# x8-oDisplayV1_3.net
KiCad netlist of a schematic drawn in EAGLE
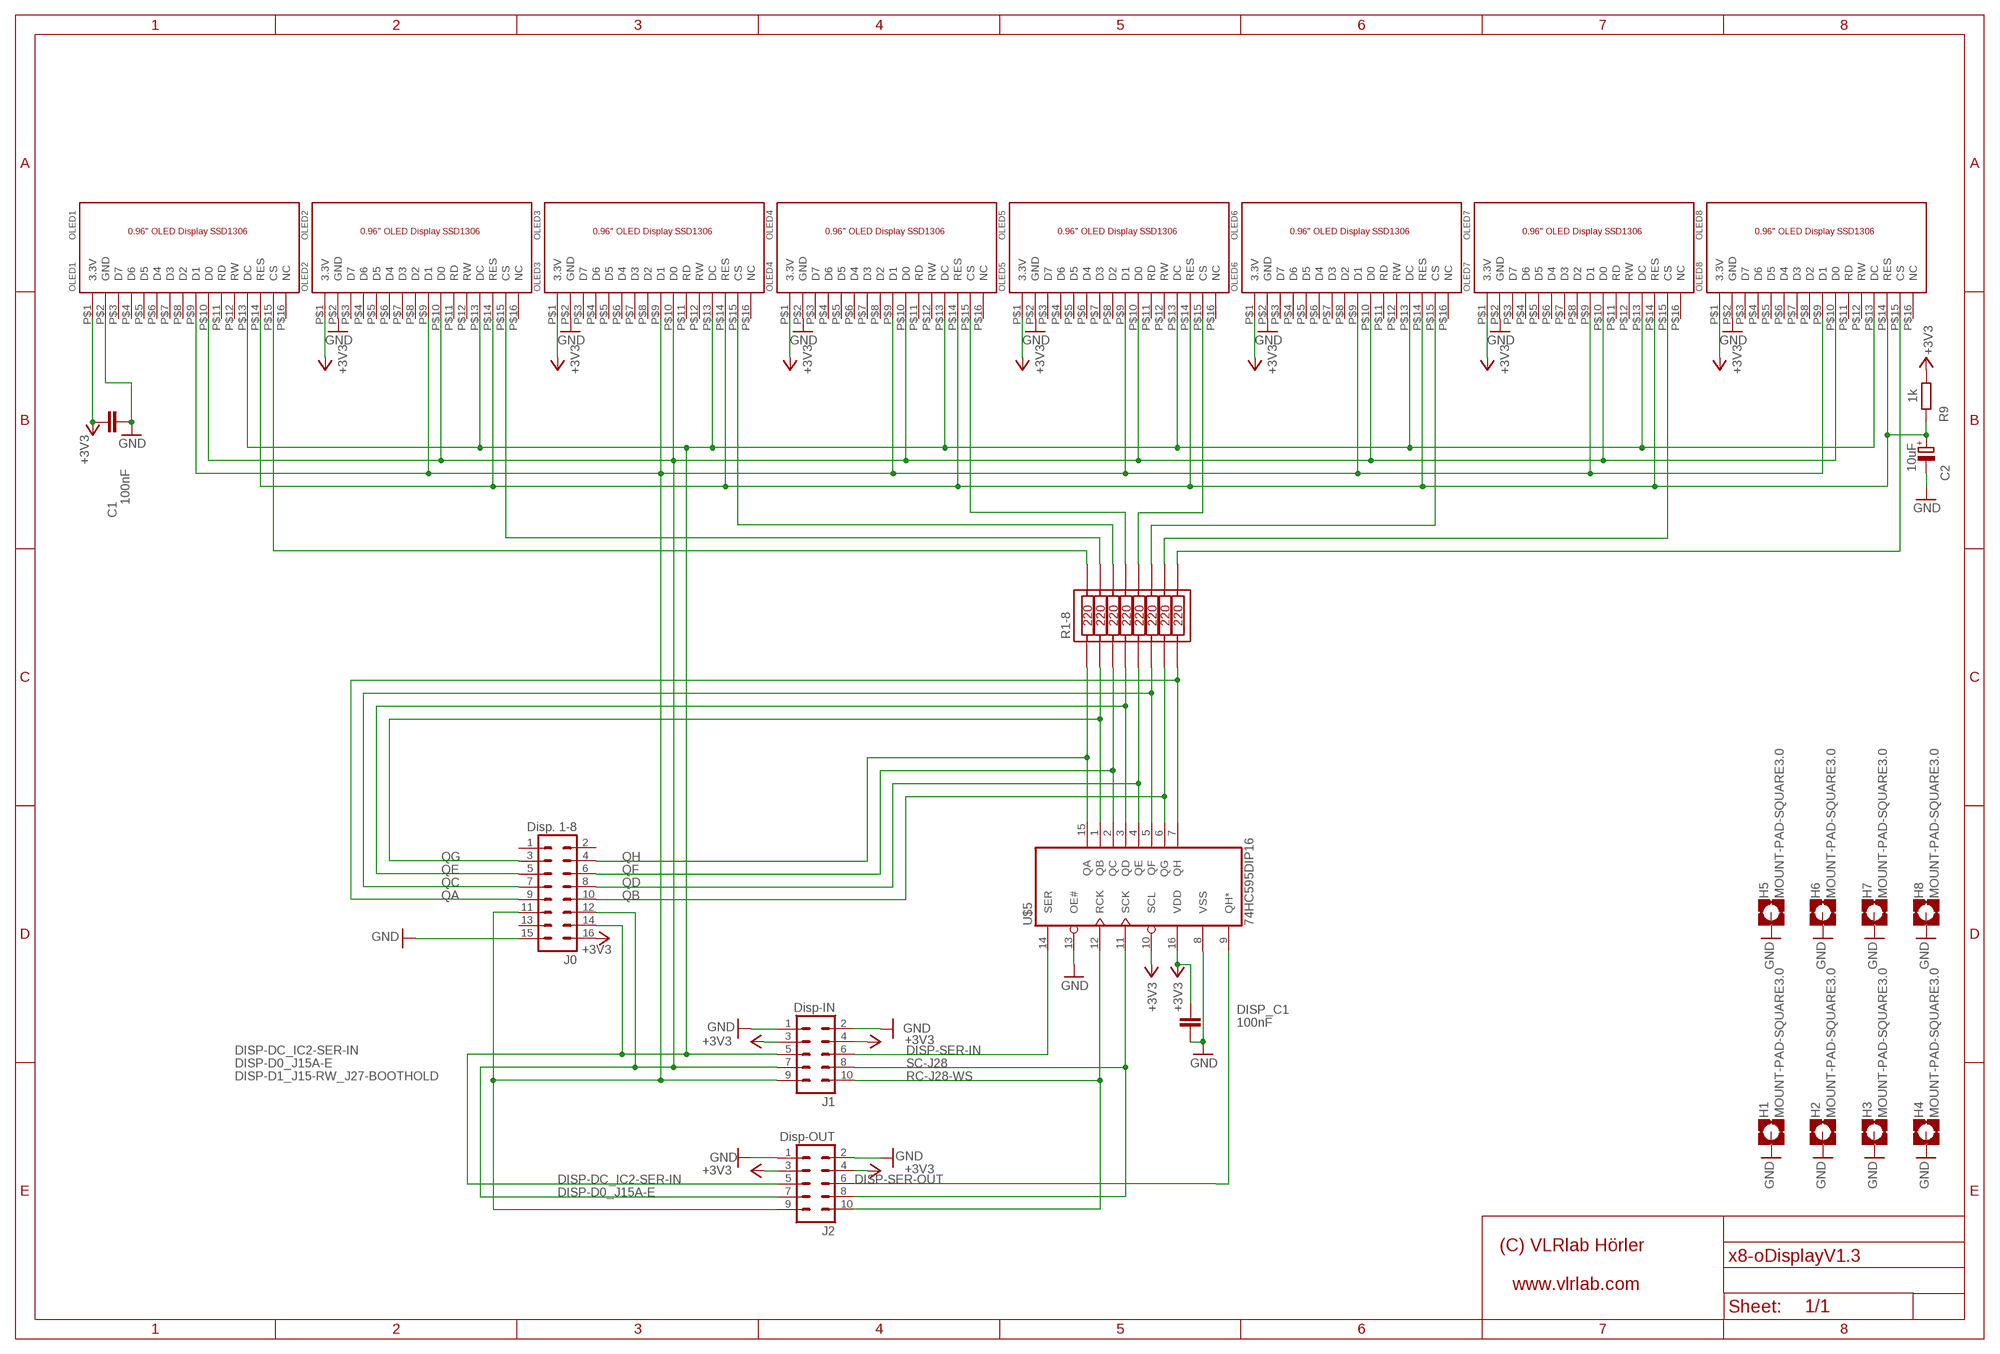
[diagram p0: schematic, sheet 1]

(export (version "E")
  (design (tool "Eeschema 10.0.6"))
  (components
    (comp (ref "C1")
      (value "100nF")
      (footprint "eagle-import:C5B3")
      (libsource (lib "eagle-import") (part "C5/3"))
    )
    (comp (ref "C2")
      (value "10uF")
      (footprint "eagle-import:E2,5-6")
      (libsource (lib "eagle-import") (part "CPOL-EUE2.5-6"))
    )
    (comp (ref "DISP_C1")
      (value "100nF")
      (footprint "eagle-import:C5B3")
      (libsource (lib "eagle-import") (part "C5/3"))
    )
    (comp (ref "H1")
      (value "MOUNT-PAD-SQUARE3.0")
      (footprint "eagle-import:3,0-PAD-SQUARE")
      (libsource (lib "eagle-import") (part "MOUNT-PAD-SQUARE3.0"))
    )
    (comp (ref "H2")
      (value "MOUNT-PAD-SQUARE3.0")
      (footprint "eagle-import:3,0-PAD-SQUARE")
      (libsource (lib "eagle-import") (part "MOUNT-PAD-SQUARE3.0"))
    )
    (comp (ref "H3")
      (value "MOUNT-PAD-SQUARE3.0")
      (footprint "eagle-import:3,0-PAD-SQUARE")
      (libsource (lib "eagle-import") (part "MOUNT-PAD-SQUARE3.0"))
    )
    (comp (ref "H4")
      (value "MOUNT-PAD-SQUARE3.0")
      (footprint "eagle-import:3,0-PAD-SQUARE")
      (libsource (lib "eagle-import") (part "MOUNT-PAD-SQUARE3.0"))
    )
    (comp (ref "H5")
      (value "MOUNT-PAD-SQUARE3.0")
      (footprint "eagle-import:3,0-PAD-SQUARE")
      (libsource (lib "eagle-import") (part "MOUNT-PAD-SQUARE3.0"))
    )
    (comp (ref "H6")
      (value "MOUNT-PAD-SQUARE3.0")
      (footprint "eagle-import:3,0-PAD-SQUARE")
      (libsource (lib "eagle-import") (part "MOUNT-PAD-SQUARE3.0"))
    )
    (comp (ref "H7")
      (value "MOUNT-PAD-SQUARE3.0")
      (footprint "eagle-import:3,0-PAD-SQUARE")
      (libsource (lib "eagle-import") (part "MOUNT-PAD-SQUARE3.0"))
    )
    (comp (ref "H8")
      (value "MOUNT-PAD-SQUARE3.0")
      (footprint "eagle-import:3,0-PAD-SQUARE")
      (libsource (lib "eagle-import") (part "MOUNT-PAD-SQUARE3.0"))
    )
    (comp (ref "J0")
      (value "Disp. 1-8")
      (footprint "eagle-import:ML16")
      (libsource (lib "eagle-import") (part "ML16"))
    )
    (comp (ref "J1")
      (value "Disp-IN")
      (footprint "eagle-import:ML10")
      (libsource (lib "eagle-import") (part "ML10"))
    )
    (comp (ref "J2")
      (value "Disp-OUT")
      (footprint "eagle-import:ML10")
      (libsource (lib "eagle-import") (part "ML10"))
    )
    (comp (ref "OLED1")
      (value "OLED1")
      (footprint "eagle-import:0.96_")
      (libsource (lib "eagle-import") (part "0.96{dblquote}OLED"))
    )
    (comp (ref "OLED2")
      (value "OLED2")
      (footprint "eagle-import:0.96_")
      (libsource (lib "eagle-import") (part "0.96{dblquote}OLED"))
    )
    (comp (ref "OLED3")
      (value "OLED3")
      (footprint "eagle-import:0.96_")
      (libsource (lib "eagle-import") (part "0.96{dblquote}OLED"))
    )
    (comp (ref "OLED4")
      (value "OLED4")
      (footprint "eagle-import:0.96_")
      (libsource (lib "eagle-import") (part "0.96{dblquote}OLED"))
    )
    (comp (ref "OLED5")
      (value "OLED5")
      (footprint "eagle-import:0.96_")
      (libsource (lib "eagle-import") (part "0.96{dblquote}OLED"))
    )
    (comp (ref "OLED6")
      (value "OLED6")
      (footprint "eagle-import:0.96_")
      (libsource (lib "eagle-import") (part "0.96{dblquote}OLED"))
    )
    (comp (ref "OLED7")
      (value "OLED7")
      (footprint "eagle-import:0.96_")
      (libsource (lib "eagle-import") (part "0.96{dblquote}OLED"))
    )
    (comp (ref "OLED8")
      (value "OLED8")
      (footprint "eagle-import:0.96_")
      (libsource (lib "eagle-import") (part "0.96{dblquote}OLED"))
    )
    (comp (ref "R1-8")
      (value "4116R")
      (footprint "eagle-import:DIL16")
      (libsource (lib "eagle-import") (part "4116R"))
    )
    (comp (ref "R9")
      (value "1k")
      (footprint "eagle-import:0204_7")
      (libsource (lib "eagle-import") (part "R-EU_0204/7"))
    )
    (comp (ref "U$5")
      (value "74HC595DIP16")
      (footprint "eagle-import:DIL16")
      (libsource (lib "eagle-import") (part "74HC595DIP16"))
    )
  )
  (nets
    (net (code "1") (name "+3V3") (class "Default")
      (node (ref "C1") (pin "1") (pinfunction "1_1") (pintype "passive"))
      (node (ref "DISP_C1") (pin "1") (pinfunction "1_1") (pintype "passive"))
      (node (ref "J0") (pin "16") (pinfunction "16_16") (pintype "passive"))
      (node (ref "J1") (pin "3") (pinfunction "3_3") (pintype "passive"))
      (node (ref "J1") (pin "4") (pinfunction "4_4") (pintype "passive"))
      (node (ref "J2") (pin "3") (pinfunction "3_3") (pintype "passive"))
      (node (ref "J2") (pin "4") (pinfunction "4_4") (pintype "passive"))
      (node (ref "OLED1") (pin "P$1") (pinfunction "3.3V_P$1") (pintype "bidirectional"))
      (node (ref "OLED2") (pin "P$1") (pinfunction "3.3V_P$1") (pintype "bidirectional"))
      (node (ref "OLED3") (pin "P$1") (pinfunction "3.3V_P$1") (pintype "bidirectional"))
      (node (ref "OLED4") (pin "P$1") (pinfunction "3.3V_P$1") (pintype "bidirectional"))
      (node (ref "OLED5") (pin "P$1") (pinfunction "3.3V_P$1") (pintype "bidirectional"))
      (node (ref "OLED6") (pin "P$1") (pinfunction "3.3V_P$1") (pintype "bidirectional"))
      (node (ref "OLED7") (pin "P$1") (pinfunction "3.3V_P$1") (pintype "bidirectional"))
      (node (ref "OLED8") (pin "P$1") (pinfunction "3.3V_P$1") (pintype "bidirectional"))
      (node (ref "R9") (pin "2") (pinfunction "2_2") (pintype "passive"))
      (node (ref "U$5") (pin "10") (pinfunction "SCL_10") (pintype "input"))
      (node (ref "U$5") (pin "16") (pinfunction "VDD_16") (pintype "power_in"))
    )
    (net (code "2") (name "/DISP-D0_J15A-E") (class "Default")
      (node (ref "J0") (pin "12") (pinfunction "12_12") (pintype "passive"))
      (node (ref "J1") (pin "7") (pinfunction "7_7") (pintype "passive"))
      (node (ref "J2") (pin "7") (pinfunction "7_7") (pintype "passive"))
      (node (ref "OLED1") (pin "P$10") (pinfunction "D0_P$10") (pintype "bidirectional"))
      (node (ref "OLED2") (pin "P$10") (pinfunction "D0_P$10") (pintype "bidirectional"))
      (node (ref "OLED3") (pin "P$10") (pinfunction "D0_P$10") (pintype "bidirectional"))
      (node (ref "OLED4") (pin "P$10") (pinfunction "D0_P$10") (pintype "bidirectional"))
      (node (ref "OLED5") (pin "P$10") (pinfunction "D0_P$10") (pintype "bidirectional"))
      (node (ref "OLED6") (pin "P$10") (pinfunction "D0_P$10") (pintype "bidirectional"))
      (node (ref "OLED7") (pin "P$10") (pinfunction "D0_P$10") (pintype "bidirectional"))
      (node (ref "OLED8") (pin "P$10") (pinfunction "D0_P$10") (pintype "bidirectional"))
    )
    (net (code "3") (name "/DISP-D1_J15-RW_J27-BOOTHOLD") (class "Default")
      (node (ref "J0") (pin "11") (pinfunction "11_11") (pintype "passive"))
      (node (ref "J1") (pin "9") (pinfunction "9_9") (pintype "passive"))
      (node (ref "J2") (pin "9") (pinfunction "9_9") (pintype "passive"))
      (node (ref "OLED1") (pin "P$9") (pinfunction "D1_P$9") (pintype "bidirectional"))
      (node (ref "OLED2") (pin "P$9") (pinfunction "D1_P$9") (pintype "bidirectional"))
      (node (ref "OLED3") (pin "P$9") (pinfunction "D1_P$9") (pintype "bidirectional"))
      (node (ref "OLED4") (pin "P$9") (pinfunction "D1_P$9") (pintype "bidirectional"))
      (node (ref "OLED5") (pin "P$9") (pinfunction "D1_P$9") (pintype "bidirectional"))
      (node (ref "OLED6") (pin "P$9") (pinfunction "D1_P$9") (pintype "bidirectional"))
      (node (ref "OLED7") (pin "P$9") (pinfunction "D1_P$9") (pintype "bidirectional"))
      (node (ref "OLED8") (pin "P$9") (pinfunction "D1_P$9") (pintype "bidirectional"))
    )
    (net (code "4") (name "/DISP-DC_IC2-SER-IN") (class "Default")
      (node (ref "J0") (pin "14") (pinfunction "14_14") (pintype "passive"))
      (node (ref "J1") (pin "5") (pinfunction "5_5") (pintype "passive"))
      (node (ref "J2") (pin "5") (pinfunction "5_5") (pintype "passive"))
      (node (ref "OLED1") (pin "P$13") (pinfunction "DC_P$13") (pintype "bidirectional"))
      (node (ref "OLED2") (pin "P$13") (pinfunction "DC_P$13") (pintype "bidirectional"))
      (node (ref "OLED3") (pin "P$13") (pinfunction "DC_P$13") (pintype "bidirectional"))
      (node (ref "OLED4") (pin "P$13") (pinfunction "DC_P$13") (pintype "bidirectional"))
      (node (ref "OLED5") (pin "P$13") (pinfunction "DC_P$13") (pintype "bidirectional"))
      (node (ref "OLED6") (pin "P$13") (pinfunction "DC_P$13") (pintype "bidirectional"))
      (node (ref "OLED7") (pin "P$13") (pinfunction "DC_P$13") (pintype "bidirectional"))
      (node (ref "OLED8") (pin "P$13") (pinfunction "DC_P$13") (pintype "bidirectional"))
    )
    (net (code "5") (name "/DISP-SER-IN") (class "Default")
      (node (ref "J1") (pin "6") (pinfunction "6_6") (pintype "passive"))
      (node (ref "U$5") (pin "14") (pinfunction "SER_14") (pintype "input"))
    )
    (net (code "6") (name "/DISP-SER-OUT") (class "Default")
      (node (ref "J2") (pin "6") (pinfunction "6_6") (pintype "passive"))
      (node (ref "U$5") (pin "9") (pinfunction "QH*_9") (pintype "tri_state"))
    )
    (net (code "7") (name "/QA") (class "Default")
      (node (ref "J0") (pin "9") (pinfunction "9_9") (pintype "passive"))
      (node (ref "R1-8") (pin "16") (pinfunction "P$16_16") (pintype "bidirectional"))
      (node (ref "U$5") (pin "7") (pinfunction "QH_7") (pintype "tri_state"))
    )
    (net (code "8") (name "/QB") (class "Default")
      (node (ref "J0") (pin "10") (pinfunction "10_10") (pintype "passive"))
      (node (ref "R1-8") (pin "15") (pinfunction "P$15_15") (pintype "bidirectional"))
      (node (ref "U$5") (pin "6") (pinfunction "QG_6") (pintype "tri_state"))
    )
    (net (code "9") (name "/QC") (class "Default")
      (node (ref "J0") (pin "7") (pinfunction "7_7") (pintype "passive"))
      (node (ref "R1-8") (pin "14") (pinfunction "P$14_14") (pintype "bidirectional"))
      (node (ref "U$5") (pin "5") (pinfunction "QF_5") (pintype "tri_state"))
    )
    (net (code "10") (name "/QD") (class "Default")
      (node (ref "J0") (pin "8") (pinfunction "8_8") (pintype "passive"))
      (node (ref "R1-8") (pin "13") (pinfunction "P$13_13") (pintype "bidirectional"))
      (node (ref "U$5") (pin "4") (pinfunction "QE_4") (pintype "tri_state"))
    )
    (net (code "11") (name "/QE") (class "Default")
      (node (ref "J0") (pin "5") (pinfunction "5_5") (pintype "passive"))
      (node (ref "R1-8") (pin "12") (pinfunction "P$12_12") (pintype "bidirectional"))
      (node (ref "U$5") (pin "3") (pinfunction "QD_3") (pintype "tri_state"))
    )
    (net (code "12") (name "/QF") (class "Default")
      (node (ref "J0") (pin "6") (pinfunction "6_6") (pintype "passive"))
      (node (ref "R1-8") (pin "11") (pinfunction "P$11_11") (pintype "bidirectional"))
      (node (ref "U$5") (pin "2") (pinfunction "QC_2") (pintype "tri_state"))
    )
    (net (code "13") (name "/QG") (class "Default")
      (node (ref "J0") (pin "3") (pinfunction "3_3") (pintype "passive"))
      (node (ref "R1-8") (pin "10") (pinfunction "P$10_10") (pintype "bidirectional"))
      (node (ref "U$5") (pin "1") (pinfunction "QB_1") (pintype "tri_state"))
    )
    (net (code "14") (name "/QH") (class "Default")
      (node (ref "J0") (pin "4") (pinfunction "4_4") (pintype "passive"))
      (node (ref "R1-8") (pin "9") (pinfunction "P$9_9") (pintype "bidirectional"))
      (node (ref "U$5") (pin "15") (pinfunction "QA_15") (pintype "tri_state"))
    )
    (net (code "15") (name "/RC-J28-WS") (class "Default")
      (node (ref "J1") (pin "10") (pinfunction "10_10") (pintype "passive"))
      (node (ref "J2") (pin "10") (pinfunction "10_10") (pintype "passive"))
      (node (ref "U$5") (pin "12") (pinfunction "RCK_12") (pintype "input"))
    )
    (net (code "16") (name "/SC-J28") (class "Default")
      (node (ref "J1") (pin "8") (pinfunction "8_8") (pintype "passive"))
      (node (ref "J2") (pin "8") (pinfunction "8_8") (pintype "passive"))
      (node (ref "U$5") (pin "11") (pinfunction "SCK_11") (pintype "input"))
    )
    (net (code "17") (name "GND") (class "Default")
      (node (ref "C1") (pin "2") (pinfunction "2_2") (pintype "passive"))
      (node (ref "C2") (pin "-") (pinfunction "-_-") (pintype "passive"))
      (node (ref "DISP_C1") (pin "2") (pinfunction "2_2") (pintype "passive"))
      (node (ref "H1") (pin "B3,0") (pinfunction "MOUNT_B3,0") (pintype "passive"))
      (node (ref "H2") (pin "B3,0") (pinfunction "MOUNT_B3,0") (pintype "passive"))
      (node (ref "H3") (pin "B3,0") (pinfunction "MOUNT_B3,0") (pintype "passive"))
      (node (ref "H4") (pin "B3,0") (pinfunction "MOUNT_B3,0") (pintype "passive"))
      (node (ref "H5") (pin "B3,0") (pinfunction "MOUNT_B3,0") (pintype "passive"))
      (node (ref "H6") (pin "B3,0") (pinfunction "MOUNT_B3,0") (pintype "passive"))
      (node (ref "H7") (pin "B3,0") (pinfunction "MOUNT_B3,0") (pintype "passive"))
      (node (ref "H8") (pin "B3,0") (pinfunction "MOUNT_B3,0") (pintype "passive"))
      (node (ref "J0") (pin "15") (pinfunction "15_15") (pintype "passive"))
      (node (ref "J1") (pin "1") (pinfunction "1_1") (pintype "passive"))
      (node (ref "J1") (pin "2") (pinfunction "2_2") (pintype "passive"))
      (node (ref "J2") (pin "1") (pinfunction "1_1") (pintype "passive"))
      (node (ref "J2") (pin "2") (pinfunction "2_2") (pintype "passive"))
      (node (ref "OLED1") (pin "P$2") (pinfunction "GND_P$2") (pintype "bidirectional"))
      (node (ref "OLED2") (pin "P$2") (pinfunction "GND_P$2") (pintype "bidirectional"))
      (node (ref "OLED3") (pin "P$2") (pinfunction "GND_P$2") (pintype "bidirectional"))
      (node (ref "OLED4") (pin "P$2") (pinfunction "GND_P$2") (pintype "bidirectional"))
      (node (ref "OLED5") (pin "P$2") (pinfunction "GND_P$2") (pintype "bidirectional"))
      (node (ref "OLED6") (pin "P$2") (pinfunction "GND_P$2") (pintype "bidirectional"))
      (node (ref "OLED7") (pin "P$2") (pinfunction "GND_P$2") (pintype "bidirectional"))
      (node (ref "OLED8") (pin "P$2") (pinfunction "GND_P$2") (pintype "bidirectional"))
      (node (ref "U$5") (pin "13") (pinfunction "OE#_13") (pintype "input"))
      (node (ref "U$5") (pin "8") (pinfunction "VSS_8") (pintype "power_in"))
    )
    (net (code "18") (name "Net-(OLED1-CS)") (class "Default")
      (node (ref "OLED1") (pin "P$15") (pinfunction "CS_P$15") (pintype "bidirectional"))
      (node (ref "R1-8") (pin "1") (pinfunction "P$1_1") (pintype "bidirectional"))
    )
    (net (code "19") (name "Net-(OLED1-RES)") (class "Default")
      (node (ref "C2") (pin "+") (pinfunction "+_+") (pintype "passive"))
      (node (ref "OLED1") (pin "P$14") (pinfunction "RES_P$14") (pintype "bidirectional"))
      (node (ref "OLED2") (pin "P$14") (pinfunction "RES_P$14") (pintype "bidirectional"))
      (node (ref "OLED3") (pin "P$14") (pinfunction "RES_P$14") (pintype "bidirectional"))
      (node (ref "OLED4") (pin "P$14") (pinfunction "RES_P$14") (pintype "bidirectional"))
      (node (ref "OLED5") (pin "P$14") (pinfunction "RES_P$14") (pintype "bidirectional"))
      (node (ref "OLED6") (pin "P$14") (pinfunction "RES_P$14") (pintype "bidirectional"))
      (node (ref "OLED7") (pin "P$14") (pinfunction "RES_P$14") (pintype "bidirectional"))
      (node (ref "OLED8") (pin "P$14") (pinfunction "RES_P$14") (pintype "bidirectional"))
      (node (ref "R9") (pin "1") (pinfunction "1_1") (pintype "passive"))
    )
    (net (code "20") (name "Net-(OLED2-CS)") (class "Default")
      (node (ref "OLED2") (pin "P$15") (pinfunction "CS_P$15") (pintype "bidirectional"))
      (node (ref "R1-8") (pin "2") (pinfunction "P$2_2") (pintype "bidirectional"))
    )
    (net (code "21") (name "Net-(OLED3-CS)") (class "Default")
      (node (ref "OLED3") (pin "P$15") (pinfunction "CS_P$15") (pintype "bidirectional"))
      (node (ref "R1-8") (pin "3") (pinfunction "P$3_3") (pintype "bidirectional"))
    )
    (net (code "22") (name "Net-(OLED4-CS)") (class "Default")
      (node (ref "OLED4") (pin "P$15") (pinfunction "CS_P$15") (pintype "bidirectional"))
      (node (ref "R1-8") (pin "4") (pinfunction "P$4_4") (pintype "bidirectional"))
    )
    (net (code "23") (name "Net-(OLED5-CS)") (class "Default")
      (node (ref "OLED5") (pin "P$15") (pinfunction "CS_P$15") (pintype "bidirectional"))
      (node (ref "R1-8") (pin "5") (pinfunction "P$5_5") (pintype "bidirectional"))
    )
    (net (code "24") (name "Net-(OLED6-CS)") (class "Default")
      (node (ref "OLED6") (pin "P$15") (pinfunction "CS_P$15") (pintype "bidirectional"))
      (node (ref "R1-8") (pin "6") (pinfunction "P$6_6") (pintype "bidirectional"))
    )
    (net (code "25") (name "Net-(OLED7-CS)") (class "Default")
      (node (ref "OLED7") (pin "P$15") (pinfunction "CS_P$15") (pintype "bidirectional"))
      (node (ref "R1-8") (pin "7") (pinfunction "P$7_7") (pintype "bidirectional"))
    )
    (net (code "26") (name "Net-(OLED8-CS)") (class "Default")
      (node (ref "OLED8") (pin "P$15") (pinfunction "CS_P$15") (pintype "bidirectional"))
      (node (ref "R1-8") (pin "8") (pinfunction "P$8_8") (pintype "bidirectional"))
    )
    (net (code "27") (name "unconnected-(J0-Pad1)") (class "Default")
      (node (ref "J0") (pin "1") (pinfunction "1_1") (pintype "passive"))
    )
    (net (code "28") (name "unconnected-(J0-Pad2)") (class "Default")
      (node (ref "J0") (pin "2") (pinfunction "2_2") (pintype "passive"))
    )
    (net (code "29") (name "unconnected-(J0-Pad13)") (class "Default")
      (node (ref "J0") (pin "13") (pinfunction "13_13") (pintype "passive"))
    )
    (net (code "30") (name "unconnected-(OLED1-D2-PadP$8)") (class "Default")
      (node (ref "OLED1") (pin "P$8") (pinfunction "D2_P$8") (pintype "bidirectional"))
    )
    (net (code "31") (name "unconnected-(OLED1-D3-PadP$7)") (class "Default")
      (node (ref "OLED1") (pin "P$7") (pinfunction "D3_P$7") (pintype "bidirectional"))
    )
    (net (code "32") (name "unconnected-(OLED1-D4-PadP$6)") (class "Default")
      (node (ref "OLED1") (pin "P$6") (pinfunction "D4_P$6") (pintype "bidirectional"))
    )
    (net (code "33") (name "unconnected-(OLED1-D5-PadP$5)") (class "Default")
      (node (ref "OLED1") (pin "P$5") (pinfunction "D5_P$5") (pintype "bidirectional"))
    )
    (net (code "34") (name "unconnected-(OLED1-D6-PadP$4)") (class "Default")
      (node (ref "OLED1") (pin "P$4") (pinfunction "D6_P$4") (pintype "bidirectional"))
    )
    (net (code "35") (name "unconnected-(OLED1-D7-PadP$3)") (class "Default")
      (node (ref "OLED1") (pin "P$3") (pinfunction "D7_P$3") (pintype "bidirectional"))
    )
    (net (code "36") (name "unconnected-(OLED1-NC-PadP$16)") (class "Default")
      (node (ref "OLED1") (pin "P$16") (pinfunction "NC_P$16") (pintype "bidirectional"))
    )
    (net (code "37") (name "unconnected-(OLED1-RD-PadP$11)") (class "Default")
      (node (ref "OLED1") (pin "P$11") (pinfunction "RD_P$11") (pintype "bidirectional"))
    )
    (net (code "38") (name "unconnected-(OLED1-RW-PadP$12)") (class "Default")
      (node (ref "OLED1") (pin "P$12") (pinfunction "RW_P$12") (pintype "bidirectional"))
    )
    (net (code "39") (name "unconnected-(OLED2-D2-PadP$8)") (class "Default")
      (node (ref "OLED2") (pin "P$8") (pinfunction "D2_P$8") (pintype "bidirectional"))
    )
    (net (code "40") (name "unconnected-(OLED2-D3-PadP$7)") (class "Default")
      (node (ref "OLED2") (pin "P$7") (pinfunction "D3_P$7") (pintype "bidirectional"))
    )
    (net (code "41") (name "unconnected-(OLED2-D4-PadP$6)") (class "Default")
      (node (ref "OLED2") (pin "P$6") (pinfunction "D4_P$6") (pintype "bidirectional"))
    )
    (net (code "42") (name "unconnected-(OLED2-D5-PadP$5)") (class "Default")
      (node (ref "OLED2") (pin "P$5") (pinfunction "D5_P$5") (pintype "bidirectional"))
    )
    (net (code "43") (name "unconnected-(OLED2-D6-PadP$4)") (class "Default")
      (node (ref "OLED2") (pin "P$4") (pinfunction "D6_P$4") (pintype "bidirectional"))
    )
    (net (code "44") (name "unconnected-(OLED2-D7-PadP$3)") (class "Default")
      (node (ref "OLED2") (pin "P$3") (pinfunction "D7_P$3") (pintype "bidirectional"))
    )
    (net (code "45") (name "unconnected-(OLED2-NC-PadP$16)") (class "Default")
      (node (ref "OLED2") (pin "P$16") (pinfunction "NC_P$16") (pintype "bidirectional"))
    )
    (net (code "46") (name "unconnected-(OLED2-RD-PadP$11)") (class "Default")
      (node (ref "OLED2") (pin "P$11") (pinfunction "RD_P$11") (pintype "bidirectional"))
    )
    (net (code "47") (name "unconnected-(OLED2-RW-PadP$12)") (class "Default")
      (node (ref "OLED2") (pin "P$12") (pinfunction "RW_P$12") (pintype "bidirectional"))
    )
    (net (code "48") (name "unconnected-(OLED3-D2-PadP$8)") (class "Default")
      (node (ref "OLED3") (pin "P$8") (pinfunction "D2_P$8") (pintype "bidirectional"))
    )
    (net (code "49") (name "unconnected-(OLED3-D3-PadP$7)") (class "Default")
      (node (ref "OLED3") (pin "P$7") (pinfunction "D3_P$7") (pintype "bidirectional"))
    )
    (net (code "50") (name "unconnected-(OLED3-D4-PadP$6)") (class "Default")
      (node (ref "OLED3") (pin "P$6") (pinfunction "D4_P$6") (pintype "bidirectional"))
    )
    (net (code "51") (name "unconnected-(OLED3-D5-PadP$5)") (class "Default")
      (node (ref "OLED3") (pin "P$5") (pinfunction "D5_P$5") (pintype "bidirectional"))
    )
    (net (code "52") (name "unconnected-(OLED3-D6-PadP$4)") (class "Default")
      (node (ref "OLED3") (pin "P$4") (pinfunction "D6_P$4") (pintype "bidirectional"))
    )
    (net (code "53") (name "unconnected-(OLED3-D7-PadP$3)") (class "Default")
      (node (ref "OLED3") (pin "P$3") (pinfunction "D7_P$3") (pintype "bidirectional"))
    )
    (net (code "54") (name "unconnected-(OLED3-NC-PadP$16)") (class "Default")
      (node (ref "OLED3") (pin "P$16") (pinfunction "NC_P$16") (pintype "bidirectional"))
    )
    (net (code "55") (name "unconnected-(OLED3-RD-PadP$11)") (class "Default")
      (node (ref "OLED3") (pin "P$11") (pinfunction "RD_P$11") (pintype "bidirectional"))
    )
    (net (code "56") (name "unconnected-(OLED3-RW-PadP$12)") (class "Default")
      (node (ref "OLED3") (pin "P$12") (pinfunction "RW_P$12") (pintype "bidirectional"))
    )
    (net (code "57") (name "unconnected-(OLED4-D2-PadP$8)") (class "Default")
      (node (ref "OLED4") (pin "P$8") (pinfunction "D2_P$8") (pintype "bidirectional"))
    )
    (net (code "58") (name "unconnected-(OLED4-D3-PadP$7)") (class "Default")
      (node (ref "OLED4") (pin "P$7") (pinfunction "D3_P$7") (pintype "bidirectional"))
    )
    (net (code "59") (name "unconnected-(OLED4-D4-PadP$6)") (class "Default")
      (node (ref "OLED4") (pin "P$6") (pinfunction "D4_P$6") (pintype "bidirectional"))
    )
    (net (code "60") (name "unconnected-(OLED4-D5-PadP$5)") (class "Default")
      (node (ref "OLED4") (pin "P$5") (pinfunction "D5_P$5") (pintype "bidirectional"))
    )
    (net (code "61") (name "unconnected-(OLED4-D6-PadP$4)") (class "Default")
      (node (ref "OLED4") (pin "P$4") (pinfunction "D6_P$4") (pintype "bidirectional"))
    )
    (net (code "62") (name "unconnected-(OLED4-D7-PadP$3)") (class "Default")
      (node (ref "OLED4") (pin "P$3") (pinfunction "D7_P$3") (pintype "bidirectional"))
    )
    (net (code "63") (name "unconnected-(OLED4-NC-PadP$16)") (class "Default")
      (node (ref "OLED4") (pin "P$16") (pinfunction "NC_P$16") (pintype "bidirectional"))
    )
    (net (code "64") (name "unconnected-(OLED4-RD-PadP$11)") (class "Default")
      (node (ref "OLED4") (pin "P$11") (pinfunction "RD_P$11") (pintype "bidirectional"))
    )
    (net (code "65") (name "unconnected-(OLED4-RW-PadP$12)") (class "Default")
      (node (ref "OLED4") (pin "P$12") (pinfunction "RW_P$12") (pintype "bidirectional"))
    )
    (net (code "66") (name "unconnected-(OLED5-D2-PadP$8)") (class "Default")
      (node (ref "OLED5") (pin "P$8") (pinfunction "D2_P$8") (pintype "bidirectional"))
    )
    (net (code "67") (name "unconnected-(OLED5-D3-PadP$7)") (class "Default")
      (node (ref "OLED5") (pin "P$7") (pinfunction "D3_P$7") (pintype "bidirectional"))
    )
    (net (code "68") (name "unconnected-(OLED5-D4-PadP$6)") (class "Default")
      (node (ref "OLED5") (pin "P$6") (pinfunction "D4_P$6") (pintype "bidirectional"))
    )
    (net (code "69") (name "unconnected-(OLED5-D5-PadP$5)") (class "Default")
      (node (ref "OLED5") (pin "P$5") (pinfunction "D5_P$5") (pintype "bidirectional"))
    )
    (net (code "70") (name "unconnected-(OLED5-D6-PadP$4)") (class "Default")
      (node (ref "OLED5") (pin "P$4") (pinfunction "D6_P$4") (pintype "bidirectional"))
    )
    (net (code "71") (name "unconnected-(OLED5-D7-PadP$3)") (class "Default")
      (node (ref "OLED5") (pin "P$3") (pinfunction "D7_P$3") (pintype "bidirectional"))
    )
    (net (code "72") (name "unconnected-(OLED5-NC-PadP$16)") (class "Default")
      (node (ref "OLED5") (pin "P$16") (pinfunction "NC_P$16") (pintype "bidirectional"))
    )
    (net (code "73") (name "unconnected-(OLED5-RD-PadP$11)") (class "Default")
      (node (ref "OLED5") (pin "P$11") (pinfunction "RD_P$11") (pintype "bidirectional"))
    )
    (net (code "74") (name "unconnected-(OLED5-RW-PadP$12)") (class "Default")
      (node (ref "OLED5") (pin "P$12") (pinfunction "RW_P$12") (pintype "bidirectional"))
    )
    (net (code "75") (name "unconnected-(OLED6-D2-PadP$8)") (class "Default")
      (node (ref "OLED6") (pin "P$8") (pinfunction "D2_P$8") (pintype "bidirectional"))
    )
    (net (code "76") (name "unconnected-(OLED6-D3-PadP$7)") (class "Default")
      (node (ref "OLED6") (pin "P$7") (pinfunction "D3_P$7") (pintype "bidirectional"))
    )
    (net (code "77") (name "unconnected-(OLED6-D4-PadP$6)") (class "Default")
      (node (ref "OLED6") (pin "P$6") (pinfunction "D4_P$6") (pintype "bidirectional"))
    )
    (net (code "78") (name "unconnected-(OLED6-D5-PadP$5)") (class "Default")
      (node (ref "OLED6") (pin "P$5") (pinfunction "D5_P$5") (pintype "bidirectional"))
    )
    (net (code "79") (name "unconnected-(OLED6-D6-PadP$4)") (class "Default")
      (node (ref "OLED6") (pin "P$4") (pinfunction "D6_P$4") (pintype "bidirectional"))
    )
    (net (code "80") (name "unconnected-(OLED6-D7-PadP$3)") (class "Default")
      (node (ref "OLED6") (pin "P$3") (pinfunction "D7_P$3") (pintype "bidirectional"))
    )
    (net (code "81") (name "unconnected-(OLED6-NC-PadP$16)") (class "Default")
      (node (ref "OLED6") (pin "P$16") (pinfunction "NC_P$16") (pintype "bidirectional"))
    )
    (net (code "82") (name "unconnected-(OLED6-RD-PadP$11)") (class "Default")
      (node (ref "OLED6") (pin "P$11") (pinfunction "RD_P$11") (pintype "bidirectional"))
    )
    (net (code "83") (name "unconnected-(OLED6-RW-PadP$12)") (class "Default")
      (node (ref "OLED6") (pin "P$12") (pinfunction "RW_P$12") (pintype "bidirectional"))
    )
    (net (code "84") (name "unconnected-(OLED7-D2-PadP$8)") (class "Default")
      (node (ref "OLED7") (pin "P$8") (pinfunction "D2_P$8") (pintype "bidirectional"))
    )
    (net (code "85") (name "unconnected-(OLED7-D3-PadP$7)") (class "Default")
      (node (ref "OLED7") (pin "P$7") (pinfunction "D3_P$7") (pintype "bidirectional"))
    )
    (net (code "86") (name "unconnected-(OLED7-D4-PadP$6)") (class "Default")
      (node (ref "OLED7") (pin "P$6") (pinfunction "D4_P$6") (pintype "bidirectional"))
    )
    (net (code "87") (name "unconnected-(OLED7-D5-PadP$5)") (class "Default")
      (node (ref "OLED7") (pin "P$5") (pinfunction "D5_P$5") (pintype "bidirectional"))
    )
    (net (code "88") (name "unconnected-(OLED7-D6-PadP$4)") (class "Default")
      (node (ref "OLED7") (pin "P$4") (pinfunction "D6_P$4") (pintype "bidirectional"))
    )
    (net (code "89") (name "unconnected-(OLED7-D7-PadP$3)") (class "Default")
      (node (ref "OLED7") (pin "P$3") (pinfunction "D7_P$3") (pintype "bidirectional"))
    )
    (net (code "90") (name "unconnected-(OLED7-NC-PadP$16)") (class "Default")
      (node (ref "OLED7") (pin "P$16") (pinfunction "NC_P$16") (pintype "bidirectional"))
    )
    (net (code "91") (name "unconnected-(OLED7-RD-PadP$11)") (class "Default")
      (node (ref "OLED7") (pin "P$11") (pinfunction "RD_P$11") (pintype "bidirectional"))
    )
    (net (code "92") (name "unconnected-(OLED7-RW-PadP$12)") (class "Default")
      (node (ref "OLED7") (pin "P$12") (pinfunction "RW_P$12") (pintype "bidirectional"))
    )
    (net (code "93") (name "unconnected-(OLED8-D2-PadP$8)") (class "Default")
      (node (ref "OLED8") (pin "P$8") (pinfunction "D2_P$8") (pintype "bidirectional"))
    )
    (net (code "94") (name "unconnected-(OLED8-D3-PadP$7)") (class "Default")
      (node (ref "OLED8") (pin "P$7") (pinfunction "D3_P$7") (pintype "bidirectional"))
    )
    (net (code "95") (name "unconnected-(OLED8-D4-PadP$6)") (class "Default")
      (node (ref "OLED8") (pin "P$6") (pinfunction "D4_P$6") (pintype "bidirectional"))
    )
    (net (code "96") (name "unconnected-(OLED8-D5-PadP$5)") (class "Default")
      (node (ref "OLED8") (pin "P$5") (pinfunction "D5_P$5") (pintype "bidirectional"))
    )
    (net (code "97") (name "unconnected-(OLED8-D6-PadP$4)") (class "Default")
      (node (ref "OLED8") (pin "P$4") (pinfunction "D6_P$4") (pintype "bidirectional"))
    )
    (net (code "98") (name "unconnected-(OLED8-D7-PadP$3)") (class "Default")
      (node (ref "OLED8") (pin "P$3") (pinfunction "D7_P$3") (pintype "bidirectional"))
    )
    (net (code "99") (name "unconnected-(OLED8-NC-PadP$16)") (class "Default")
      (node (ref "OLED8") (pin "P$16") (pinfunction "NC_P$16") (pintype "bidirectional"))
    )
    (net (code "100") (name "unconnected-(OLED8-RD-PadP$11)") (class "Default")
      (node (ref "OLED8") (pin "P$11") (pinfunction "RD_P$11") (pintype "bidirectional"))
    )
    (net (code "101") (name "unconnected-(OLED8-RW-PadP$12)") (class "Default")
      (node (ref "OLED8") (pin "P$12") (pinfunction "RW_P$12") (pintype "bidirectional"))
    )
  )
)
